# SoC_BootMode.net
KiCad netlist of a schematic drawn in Altium Designer
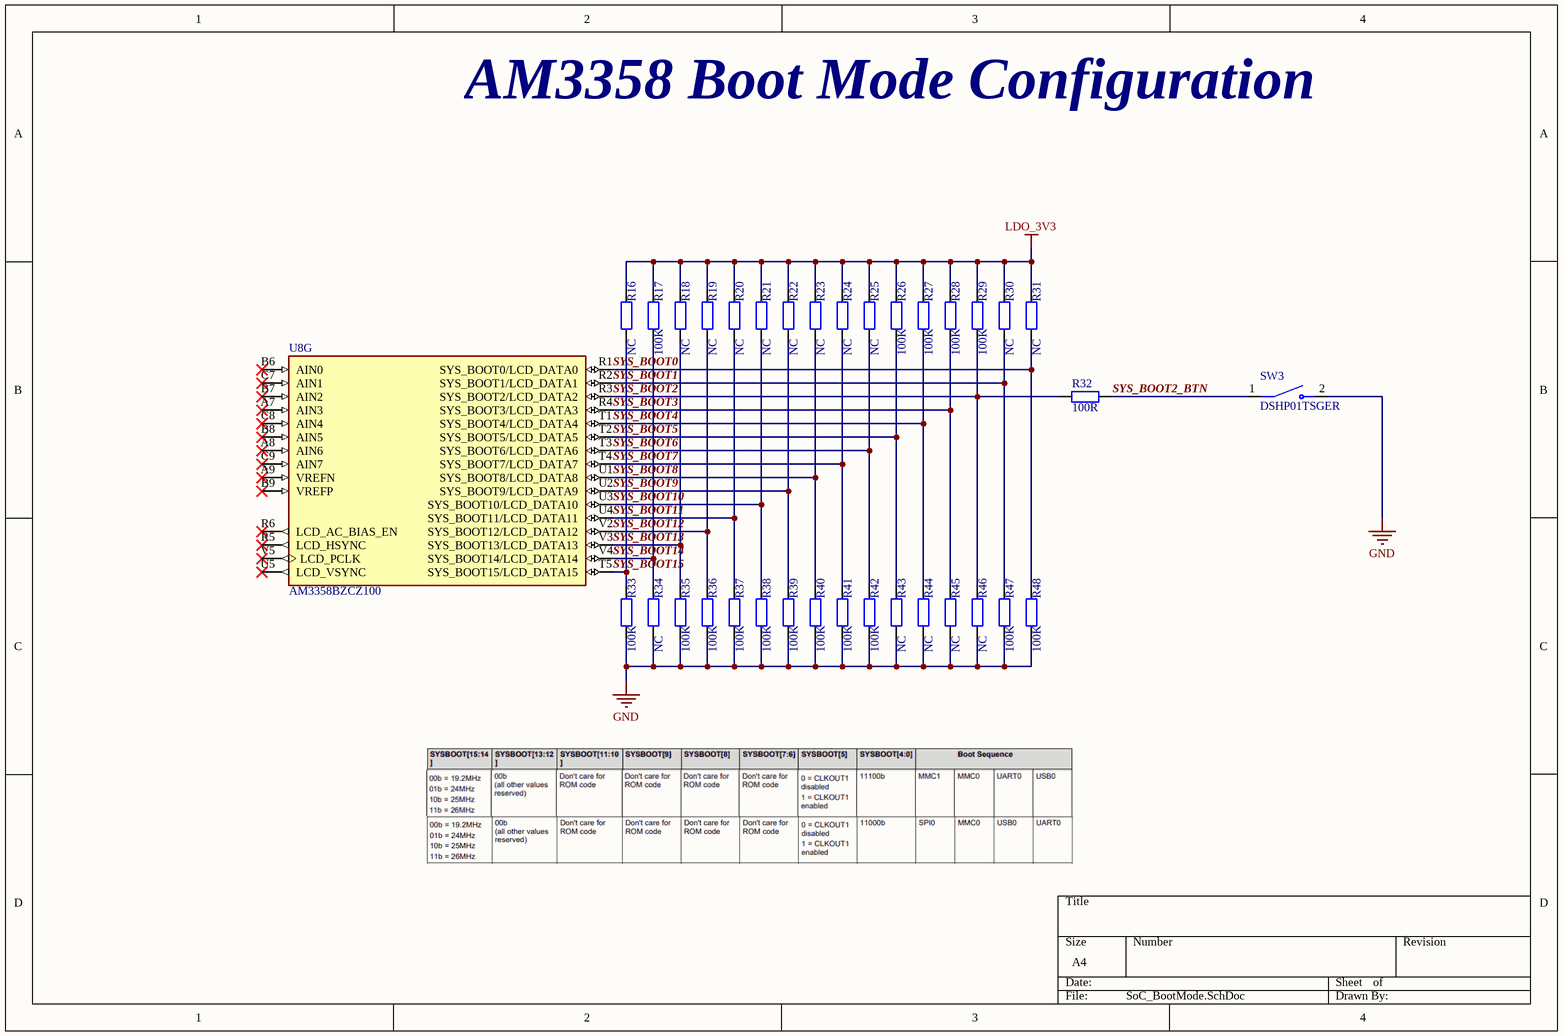
[diagram p0: SoC_BootMode.SchDoc]

(export (version "E")
  (design (tool "Eeschema 10.0.6"))
  (components
    (comp (ref "R16")
      (value "NC")
      (footprint "R_0402")
      (description "Resistor 0402 SMD")
      (libsource (lib "tor1kkLib") (part "R_0402"))
    )
    (comp (ref "R17")
      (value "100K")
      (footprint "R_0402")
      (description "Resistor 0402 SMD")
      (libsource (lib "tor1kkLib") (part "R_0402"))
    )
    (comp (ref "R18")
      (value "NC")
      (footprint "R_0402")
      (description "Resistor 0402 SMD")
      (libsource (lib "tor1kkLib") (part "R_0402"))
    )
    (comp (ref "R19")
      (value "NC")
      (footprint "R_0402")
      (description "Resistor 0402 SMD")
      (libsource (lib "tor1kkLib") (part "R_0402"))
    )
    (comp (ref "R20")
      (value "NC")
      (footprint "R_0402")
      (description "Resistor 0402 SMD")
      (libsource (lib "tor1kkLib") (part "R_0402"))
    )
    (comp (ref "R21")
      (value "NC")
      (footprint "R_0402")
      (description "Resistor 0402 SMD")
      (libsource (lib "tor1kkLib") (part "R_0402"))
    )
    (comp (ref "R22")
      (value "NC")
      (footprint "R_0402")
      (description "Resistor 0402 SMD")
      (libsource (lib "tor1kkLib") (part "R_0402"))
    )
    (comp (ref "R23")
      (value "NC")
      (footprint "R_0402")
      (description "Resistor 0402 SMD")
      (libsource (lib "tor1kkLib") (part "R_0402"))
    )
    (comp (ref "R24")
      (value "NC")
      (footprint "R_0402")
      (description "Resistor 0402 SMD")
      (libsource (lib "tor1kkLib") (part "R_0402"))
    )
    (comp (ref "R25")
      (value "NC")
      (footprint "R_0402")
      (description "Resistor 0402 SMD")
      (libsource (lib "tor1kkLib") (part "R_0402"))
    )
    (comp (ref "R26")
      (value "100K")
      (footprint "R_0402")
      (description "Resistor 0402 SMD")
      (libsource (lib "tor1kkLib") (part "R_0402"))
    )
    (comp (ref "R27")
      (value "100K")
      (footprint "R_0402")
      (description "Resistor 0402 SMD")
      (libsource (lib "tor1kkLib") (part "R_0402"))
    )
    (comp (ref "R28")
      (value "100K")
      (footprint "R_0402")
      (description "Resistor 0402 SMD")
      (libsource (lib "tor1kkLib") (part "R_0402"))
    )
    (comp (ref "R29")
      (value "100K")
      (footprint "R_0402")
      (description "Resistor 0402 SMD")
      (libsource (lib "tor1kkLib") (part "R_0402"))
    )
    (comp (ref "R30")
      (value "NC")
      (footprint "R_0402")
      (description "Resistor 0402 SMD")
      (libsource (lib "tor1kkLib") (part "R_0402"))
    )
    (comp (ref "R31")
      (value "NC")
      (footprint "R_0402")
      (description "Resistor 0402 SMD")
      (libsource (lib "tor1kkLib") (part "R_0402"))
    )
    (comp (ref "R32")
      (value "100R")
      (footprint "R_0402")
      (description "Resistor 0402 SMD")
      (libsource (lib "") (part "R_0402_1"))
    )
    (comp (ref "R33")
      (value "100K")
      (footprint "R_0402")
      (description "Resistor 0402 SMD")
      (libsource (lib "tor1kkLib") (part "R_0402"))
    )
    (comp (ref "R34")
      (value "NC")
      (footprint "R_0402")
      (description "Resistor 0402 SMD")
      (libsource (lib "tor1kkLib") (part "R_0402"))
    )
    (comp (ref "R35")
      (value "100K")
      (footprint "R_0402")
      (description "Resistor 0402 SMD")
      (libsource (lib "tor1kkLib") (part "R_0402"))
    )
    (comp (ref "R36")
      (value "100K")
      (footprint "R_0402")
      (description "Resistor 0402 SMD")
      (libsource (lib "tor1kkLib") (part "R_0402"))
    )
    (comp (ref "R37")
      (value "100K")
      (footprint "R_0402")
      (description "Resistor 0402 SMD")
      (libsource (lib "tor1kkLib") (part "R_0402"))
    )
    (comp (ref "R38")
      (value "100K")
      (footprint "R_0402")
      (description "Resistor 0402 SMD")
      (libsource (lib "tor1kkLib") (part "R_0402"))
    )
    (comp (ref "R39")
      (value "100K")
      (footprint "R_0402")
      (description "Resistor 0402 SMD")
      (libsource (lib "tor1kkLib") (part "R_0402"))
    )
    (comp (ref "R40")
      (value "100K")
      (footprint "R_0402")
      (description "Resistor 0402 SMD")
      (libsource (lib "tor1kkLib") (part "R_0402"))
    )
    (comp (ref "R41")
      (value "100K")
      (footprint "R_0402")
      (description "Resistor 0402 SMD")
      (libsource (lib "tor1kkLib") (part "R_0402"))
    )
    (comp (ref "R42")
      (value "100K")
      (footprint "R_0402")
      (description "Resistor 0402 SMD")
      (libsource (lib "tor1kkLib") (part "R_0402"))
    )
    (comp (ref "R43")
      (value "NC")
      (footprint "R_0402")
      (description "Resistor 0402 SMD")
      (libsource (lib "tor1kkLib") (part "R_0402"))
    )
    (comp (ref "R44")
      (value "NC")
      (footprint "R_0402")
      (description "Resistor 0402 SMD")
      (libsource (lib "tor1kkLib") (part "R_0402"))
    )
    (comp (ref "R45")
      (value "NC")
      (footprint "R_0402")
      (description "Resistor 0402 SMD")
      (libsource (lib "tor1kkLib") (part "R_0402"))
    )
    (comp (ref "R46")
      (value "NC")
      (footprint "R_0402")
      (description "Resistor 0402 SMD")
      (libsource (lib "tor1kkLib") (part "R_0402"))
    )
    (comp (ref "R47")
      (value "100K")
      (footprint "R_0402")
      (description "Resistor 0402 SMD")
      (libsource (lib "tor1kkLib") (part "R_0402"))
    )
    (comp (ref "R48")
      (value "100K")
      (footprint "R_0402")
      (description "Resistor 0402 SMD")
      (libsource (lib "tor1kkLib") (part "R_0402"))
    )
    (comp (ref "SW3")
      (value "DSHP01TSGER")
      (footprint "DSHP01TSGER")
      (description "1 Digit SPST 24V Black 25mA 3000 Times SMD,2.9x5.4mm DIP Switches ROHS")
      (fields (field (name "MANUFACTURER") "kangshen"))
      (libsource (lib "tor1kkLib") (part "DSHP01TSGER"))
    )
    (comp (ref "U8")
      (value "AM3358BZCZ100")
      (footprint "BGA324C80P18X18_1500X1500X140")
      (description "ARM-ASeries 1GHz NFBGA-324 Microcontrollers (MCU/MPU/SOC) ROHS")
      (fields (field (name "MANUFACTURER") "Texas Instruments"))
      (libsource (lib "tor1kkLib") (part "AM3358BZCZ100"))
    )
  )
  (nets
    (net (code "1") (name "/SYS_BOOT0") (class "Default")
      (node (ref "R31") (pin "1") (pintype "passive"))
      (node (ref "R48") (pin "2") (pintype "passive"))
      (node (ref "U8") (pin "R1") (pinfunction "SYS_BOOT0/LCD_DATA0_R1") (pintype "bidirectional"))
    )
    (net (code "2") (name "/SYS_BOOT1") (class "Default")
      (node (ref "R30") (pin "1") (pintype "passive"))
      (node (ref "R47") (pin "2") (pintype "passive"))
      (node (ref "U8") (pin "R2") (pinfunction "SYS_BOOT1/LCD_DATA1_R2") (pintype "bidirectional"))
    )
    (net (code "3") (name "/SYS_BOOT2") (class "Default")
      (node (ref "R29") (pin "1") (pintype "passive"))
      (node (ref "R32") (pin "1") (pintype "passive"))
      (node (ref "R46") (pin "2") (pintype "passive"))
      (node (ref "U8") (pin "R3") (pinfunction "SYS_BOOT2/LCD_DATA2_R3") (pintype "bidirectional"))
    )
    (net (code "4") (name "/SYS_BOOT2_BTN") (class "Default")
      (node (ref "R32") (pin "2") (pintype "passive"))
      (node (ref "SW3") (pin "1") (pinfunction "COM_1") (pintype "passive"))
    )
    (net (code "5") (name "/SYS_BOOT3") (class "Default")
      (node (ref "R28") (pin "1") (pintype "passive"))
      (node (ref "R45") (pin "2") (pintype "passive"))
      (node (ref "U8") (pin "R4") (pinfunction "SYS_BOOT3/LCD_DATA3_R4") (pintype "bidirectional"))
    )
    (net (code "6") (name "/SYS_BOOT4") (class "Default")
      (node (ref "R27") (pin "1") (pintype "passive"))
      (node (ref "R44") (pin "2") (pintype "passive"))
      (node (ref "U8") (pin "T1") (pinfunction "SYS_BOOT4/LCD_DATA4_T1") (pintype "bidirectional"))
    )
    (net (code "7") (name "/SYS_BOOT5") (class "Default")
      (node (ref "R26") (pin "1") (pintype "passive"))
      (node (ref "R43") (pin "2") (pintype "passive"))
      (node (ref "U8") (pin "T2") (pinfunction "SYS_BOOT5/LCD_DATA5_T2") (pintype "bidirectional"))
    )
    (net (code "8") (name "/SYS_BOOT6") (class "Default")
      (node (ref "R25") (pin "1") (pintype "passive"))
      (node (ref "R42") (pin "2") (pintype "passive"))
      (node (ref "U8") (pin "T3") (pinfunction "SYS_BOOT6/LCD_DATA6_T3") (pintype "bidirectional"))
    )
    (net (code "9") (name "/SYS_BOOT7") (class "Default")
      (node (ref "R24") (pin "1") (pintype "passive"))
      (node (ref "R41") (pin "2") (pintype "passive"))
      (node (ref "U8") (pin "T4") (pinfunction "SYS_BOOT7/LCD_DATA7_T4") (pintype "bidirectional"))
    )
    (net (code "10") (name "/SYS_BOOT8") (class "Default")
      (node (ref "R23") (pin "1") (pintype "passive"))
      (node (ref "R40") (pin "2") (pintype "passive"))
      (node (ref "U8") (pin "U1") (pinfunction "SYS_BOOT8/LCD_DATA8_U1") (pintype "bidirectional"))
    )
    (net (code "11") (name "/SYS_BOOT9") (class "Default")
      (node (ref "R22") (pin "1") (pintype "passive"))
      (node (ref "R39") (pin "2") (pintype "passive"))
      (node (ref "U8") (pin "U2") (pinfunction "SYS_BOOT9/LCD_DATA9_U2") (pintype "bidirectional"))
    )
    (net (code "12") (name "/SYS_BOOT10") (class "Default")
      (node (ref "R21") (pin "1") (pintype "passive"))
      (node (ref "R38") (pin "2") (pintype "passive"))
      (node (ref "U8") (pin "U3") (pinfunction "SYS_BOOT10/LCD_DATA10_U3") (pintype "bidirectional"))
    )
    (net (code "13") (name "/SYS_BOOT11") (class "Default")
      (node (ref "R20") (pin "1") (pintype "passive"))
      (node (ref "R37") (pin "2") (pintype "passive"))
      (node (ref "U8") (pin "U4") (pinfunction "SYS_BOOT11/LCD_DATA11_U4") (pintype "bidirectional"))
    )
    (net (code "14") (name "/SYS_BOOT12") (class "Default")
      (node (ref "R19") (pin "1") (pintype "passive"))
      (node (ref "R36") (pin "2") (pintype "passive"))
      (node (ref "U8") (pin "V2") (pinfunction "SYS_BOOT12/LCD_DATA12_V2") (pintype "bidirectional"))
    )
    (net (code "15") (name "/SYS_BOOT13") (class "Default")
      (node (ref "R18") (pin "1") (pintype "passive"))
      (node (ref "R35") (pin "2") (pintype "passive"))
      (node (ref "U8") (pin "V3") (pinfunction "SYS_BOOT13/LCD_DATA13_V3") (pintype "bidirectional"))
    )
    (net (code "16") (name "/SYS_BOOT14") (class "Default")
      (node (ref "R17") (pin "1") (pintype "passive"))
      (node (ref "R34") (pin "2") (pintype "passive"))
      (node (ref "U8") (pin "V4") (pinfunction "SYS_BOOT14/LCD_DATA14_V4") (pintype "bidirectional"))
    )
    (net (code "17") (name "/SYS_BOOT15") (class "Default")
      (node (ref "R16") (pin "1") (pintype "passive"))
      (node (ref "R33") (pin "2") (pintype "passive"))
      (node (ref "U8") (pin "T5") (pinfunction "SYS_BOOT15/LCD_DATA15_T5") (pintype "bidirectional"))
    )
    (net (code "18") (name "GND") (class "Default")
      (node (ref "R33") (pin "1") (pintype "passive"))
      (node (ref "R34") (pin "1") (pintype "passive"))
      (node (ref "R35") (pin "1") (pintype "passive"))
      (node (ref "R36") (pin "1") (pintype "passive"))
      (node (ref "R37") (pin "1") (pintype "passive"))
      (node (ref "R38") (pin "1") (pintype "passive"))
      (node (ref "R39") (pin "1") (pintype "passive"))
      (node (ref "R40") (pin "1") (pintype "passive"))
      (node (ref "R41") (pin "1") (pintype "passive"))
      (node (ref "R42") (pin "1") (pintype "passive"))
      (node (ref "R43") (pin "1") (pintype "passive"))
      (node (ref "R44") (pin "1") (pintype "passive"))
      (node (ref "R45") (pin "1") (pintype "passive"))
      (node (ref "R46") (pin "1") (pintype "passive"))
      (node (ref "R47") (pin "1") (pintype "passive"))
      (node (ref "R48") (pin "1") (pintype "passive"))
      (node (ref "SW3") (pin "2") (pinfunction "NO_2") (pintype "passive"))
    )
    (net (code "19") (name "LDO_3V3") (class "Default")
      (node (ref "R16") (pin "2") (pintype "passive"))
      (node (ref "R17") (pin "2") (pintype "passive"))
      (node (ref "R18") (pin "2") (pintype "passive"))
      (node (ref "R19") (pin "2") (pintype "passive"))
      (node (ref "R20") (pin "2") (pintype "passive"))
      (node (ref "R21") (pin "2") (pintype "passive"))
      (node (ref "R22") (pin "2") (pintype "passive"))
      (node (ref "R23") (pin "2") (pintype "passive"))
      (node (ref "R24") (pin "2") (pintype "passive"))
      (node (ref "R25") (pin "2") (pintype "passive"))
      (node (ref "R26") (pin "2") (pintype "passive"))
      (node (ref "R27") (pin "2") (pintype "passive"))
      (node (ref "R28") (pin "2") (pintype "passive"))
      (node (ref "R29") (pin "2") (pintype "passive"))
      (node (ref "R30") (pin "2") (pintype "passive"))
      (node (ref "R31") (pin "2") (pintype "passive"))
    )
    (net (code "20") (name "unconnected-(U8G-AIN0-PadB6)") (class "Default")
      (node (ref "U8") (pin "B6") (pinfunction "AIN0_B6") (pintype "input+no_connect"))
    )
    (net (code "21") (name "unconnected-(U8G-AIN1-PadC7)") (class "Default")
      (node (ref "U8") (pin "C7") (pinfunction "AIN1_C7") (pintype "input+no_connect"))
    )
    (net (code "22") (name "unconnected-(U8G-AIN2-PadB7)") (class "Default")
      (node (ref "U8") (pin "B7") (pinfunction "AIN2_B7") (pintype "input+no_connect"))
    )
    (net (code "23") (name "unconnected-(U8G-AIN3-PadA7)") (class "Default")
      (node (ref "U8") (pin "A7") (pinfunction "AIN3_A7") (pintype "input+no_connect"))
    )
    (net (code "24") (name "unconnected-(U8G-AIN4-PadC8)") (class "Default")
      (node (ref "U8") (pin "C8") (pinfunction "AIN4_C8") (pintype "input+no_connect"))
    )
    (net (code "25") (name "unconnected-(U8G-AIN5-PadB8)") (class "Default")
      (node (ref "U8") (pin "B8") (pinfunction "AIN5_B8") (pintype "input+no_connect"))
    )
    (net (code "26") (name "unconnected-(U8G-AIN6-PadA8)") (class "Default")
      (node (ref "U8") (pin "A8") (pinfunction "AIN6_A8") (pintype "input+no_connect"))
    )
    (net (code "27") (name "unconnected-(U8G-AIN7-PadC9)") (class "Default")
      (node (ref "U8") (pin "C9") (pinfunction "AIN7_C9") (pintype "input+no_connect"))
    )
    (net (code "28") (name "unconnected-(U8G-LCD_AC_BIAS_EN-PadR6)") (class "Default")
      (node (ref "U8") (pin "R6") (pinfunction "LCD_AC_BIAS_EN_R6") (pintype "output+no_connect"))
    )
    (net (code "29") (name "unconnected-(U8G-LCD_HSYNC-PadR5)") (class "Default")
      (node (ref "U8") (pin "R5") (pinfunction "LCD_HSYNC_R5") (pintype "output+no_connect"))
    )
    (net (code "30") (name "unconnected-(U8G-LCD_PCLK-PadV5)") (class "Default")
      (node (ref "U8") (pin "V5") (pinfunction "LCD_PCLK_V5") (pintype "output+no_connect"))
    )
    (net (code "31") (name "unconnected-(U8G-LCD_VSYNC-PadU5)") (class "Default")
      (node (ref "U8") (pin "U5") (pinfunction "LCD_VSYNC_U5") (pintype "output+no_connect"))
    )
    (net (code "32") (name "unconnected-(U8G-VREFN-PadA9)") (class "Default")
      (node (ref "U8") (pin "A9") (pinfunction "VREFN_A9") (pintype "input+no_connect"))
    )
    (net (code "33") (name "unconnected-(U8G-VREFP-PadB9)") (class "Default")
      (node (ref "U8") (pin "B9") (pinfunction "VREFP_B9") (pintype "input+no_connect"))
    )
  )
)
